# electrical_scheme.net
KiCad netlist of a schematic drawn in EAGLE
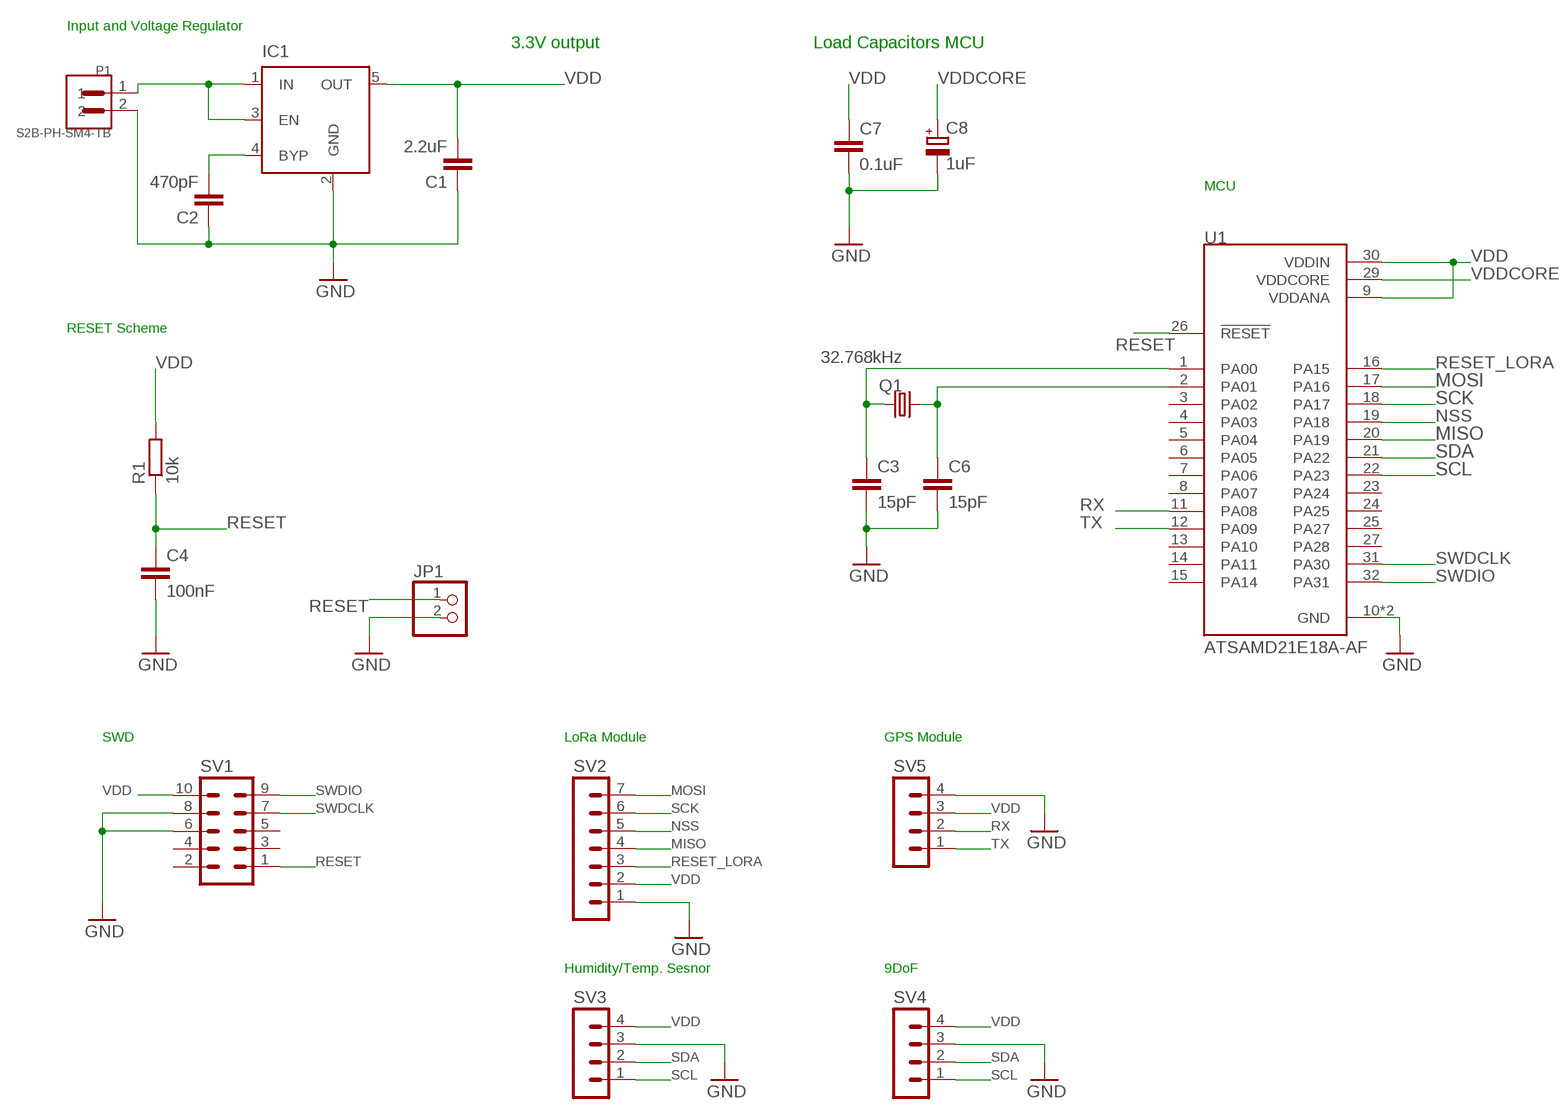
[diagram p0: schematic, sheet 1]

(export (version "E")
  (design (tool "Eeschema 10.0.6"))
  (components
    (comp (ref "C1")
      (value "2.2uF")
      (footprint "eagle-import:C1608")
      (libsource (lib "eagle-import") (part "C-EUC1608"))
    )
    (comp (ref "C2")
      (value "470pF")
      (footprint "eagle-import:C1608")
      (libsource (lib "eagle-import") (part "C-EUC1608"))
    )
    (comp (ref "C3")
      (value "15pF")
      (footprint "eagle-import:C1608")
      (libsource (lib "eagle-import") (part "C-EUC1608"))
    )
    (comp (ref "C4")
      (value "100nF")
      (footprint "eagle-import:C1608")
      (libsource (lib "eagle-import") (part "C-EUC1608"))
    )
    (comp (ref "C6")
      (value "15pF")
      (footprint "eagle-import:C1608")
      (libsource (lib "eagle-import") (part "C-EUC1608"))
    )
    (comp (ref "C7")
      (value "0.1uF")
      (footprint "eagle-import:C1608")
      (libsource (lib "eagle-import") (part "C-EUC1608"))
    )
    (comp (ref "C8")
      (value "1uF")
      (footprint "eagle-import:C_6032-28R")
      (libsource (lib "eagle-import") (part "CPOL-EUC/6032-28R"))
    )
    (comp (ref "IC1")
      (value "MIC5219XX")
      (footprint "eagle-import:SOT23-5")
      (libsource (lib "eagle-import") (part "MIC5219XX"))
    )
    (comp (ref "JP1")
      (value "PINHD-1X2")
      (footprint "eagle-import:1X02")
      (libsource (lib "eagle-import") (part "PINHD-1X2"))
    )
    (comp (ref "P1")
      (value "S2B-PH-SM4-TB")
      (footprint "eagle-import:JST_S2B-PH-SM4-TB")
      (fields (field (name "MF") "JST Sales"))
      (libsource (lib "eagle-import") (part "S2B-PH-SM4-TB"))
    )
    (comp (ref "Q1")
      (value "32.768kHz")
      (footprint "eagle-import:MC-306")
      (fields (field (name "MPN") "MC-306 60.0KHZ  100PPM ,12.5PF"))
      (libsource (lib "eagle-import") (part "MC-306"))
    )
    (comp (ref "R1")
      (value "10k")
      (footprint "eagle-import:R0805")
      (libsource (lib "eagle-import") (part "R-EU_R0805"))
    )
    (comp (ref "SV1")
      (value "MA05-2")
      (footprint "eagle-import:MA05-2")
      (libsource (lib "eagle-import") (part "MA05-2"))
    )
    (comp (ref "SV2")
      (value "MA07-1")
      (footprint "eagle-import:MA07-1")
      (libsource (lib "eagle-import") (part "MA07-1"))
    )
    (comp (ref "SV3")
      (value "MA04-1")
      (footprint "eagle-import:MA04-1")
      (libsource (lib "eagle-import") (part "MA04-1"))
    )
    (comp (ref "SV4")
      (value "MA04-1")
      (footprint "eagle-import:MA04-1")
      (libsource (lib "eagle-import") (part "MA04-1"))
    )
    (comp (ref "SV5")
      (value "MA04-1")
      (footprint "eagle-import:MA04-1")
      (libsource (lib "eagle-import") (part "MA04-1"))
    )
    (comp (ref "U1")
      (value "ATSAMD21E18A-AF")
      (footprint "eagle-import:QFP80P900X900X120-32N")
      (fields (field (name "MF") "Microchip"))
      (libsource (lib "eagle-import") (part "ATSAMD21E18A-AF"))
    )
  )
  (nets
    (net (code "1") (name "/MISO") (class "Default")
      (node (ref "SV2") (pin "4") (pinfunction "4_4") (pintype "passive"))
      (node (ref "U1") (pin "20") (pinfunction "PA19_20") (pintype "bidirectional"))
    )
    (net (code "2") (name "/MOSI") (class "Default")
      (node (ref "SV2") (pin "7") (pinfunction "7_7") (pintype "passive"))
      (node (ref "U1") (pin "17") (pinfunction "PA16_17") (pintype "bidirectional"))
    )
    (net (code "3") (name "/NSS") (class "Default")
      (node (ref "SV2") (pin "5") (pinfunction "5_5") (pintype "passive"))
      (node (ref "U1") (pin "19") (pinfunction "PA18_19") (pintype "bidirectional"))
    )
    (net (code "4") (name "/RESET") (class "Default")
      (node (ref "C4") (pin "1") (pinfunction "1_1") (pintype "passive"))
      (node (ref "JP1") (pin "1") (pinfunction "1_1") (pintype "passive"))
      (node (ref "R1") (pin "1") (pinfunction "1_1") (pintype "passive"))
      (node (ref "SV1") (pin "1") (pinfunction "1_1") (pintype "passive"))
      (node (ref "U1") (pin "26") (pinfunction "~{RESET}_26") (pintype "input"))
    )
    (net (code "5") (name "/RESET_LORA") (class "Default")
      (node (ref "SV2") (pin "3") (pinfunction "3_3") (pintype "passive"))
      (node (ref "U1") (pin "16") (pinfunction "PA15_16") (pintype "bidirectional"))
    )
    (net (code "6") (name "/RX") (class "Default")
      (node (ref "SV5") (pin "2") (pinfunction "2_2") (pintype "passive"))
      (node (ref "U1") (pin "11") (pinfunction "PA08_11") (pintype "bidirectional"))
    )
    (net (code "7") (name "/SCK") (class "Default")
      (node (ref "SV2") (pin "6") (pinfunction "6_6") (pintype "passive"))
      (node (ref "U1") (pin "18") (pinfunction "PA17_18") (pintype "bidirectional"))
    )
    (net (code "8") (name "/SCL") (class "Default")
      (node (ref "SV3") (pin "1") (pinfunction "1_1") (pintype "passive"))
      (node (ref "SV4") (pin "1") (pinfunction "1_1") (pintype "passive"))
      (node (ref "U1") (pin "22") (pinfunction "PA23_22") (pintype "bidirectional"))
    )
    (net (code "9") (name "/SDA") (class "Default")
      (node (ref "SV3") (pin "2") (pinfunction "2_2") (pintype "passive"))
      (node (ref "SV4") (pin "2") (pinfunction "2_2") (pintype "passive"))
      (node (ref "U1") (pin "21") (pinfunction "PA22_21") (pintype "bidirectional"))
    )
    (net (code "10") (name "/SWDCLK") (class "Default")
      (node (ref "SV1") (pin "7") (pinfunction "7_7") (pintype "passive"))
      (node (ref "U1") (pin "31") (pinfunction "PA30_31") (pintype "bidirectional"))
    )
    (net (code "11") (name "/SWDIO") (class "Default")
      (node (ref "SV1") (pin "9") (pinfunction "9_9") (pintype "passive"))
      (node (ref "U1") (pin "32") (pinfunction "PA31_32") (pintype "bidirectional"))
    )
    (net (code "12") (name "/TX") (class "Default")
      (node (ref "SV5") (pin "1") (pinfunction "1_1") (pintype "passive"))
      (node (ref "U1") (pin "12") (pinfunction "PA09_12") (pintype "bidirectional"))
    )
    (net (code "13") (name "/VDD") (class "Default")
      (node (ref "C1") (pin "2") (pinfunction "2_2") (pintype "passive"))
      (node (ref "C7") (pin "1") (pinfunction "1_1") (pintype "passive"))
      (node (ref "IC1") (pin "5") (pinfunction "OUT_5") (pintype "output"))
      (node (ref "R1") (pin "2") (pinfunction "2_2") (pintype "passive"))
      (node (ref "SV1") (pin "10") (pinfunction "10_10") (pintype "passive"))
      (node (ref "SV2") (pin "2") (pinfunction "2_2") (pintype "passive"))
      (node (ref "SV3") (pin "4") (pinfunction "4_4") (pintype "passive"))
      (node (ref "SV4") (pin "4") (pinfunction "4_4") (pintype "passive"))
      (node (ref "SV5") (pin "3") (pinfunction "3_3") (pintype "passive"))
      (node (ref "U1") (pin "30") (pinfunction "VDDIN_30") (pintype "power_in"))
      (node (ref "U1") (pin "9") (pinfunction "VDDANA_9") (pintype "power_in"))
    )
    (net (code "14") (name "/VDDCORE") (class "Default")
      (node (ref "C8") (pin "+") (pinfunction "+_+") (pintype "passive"))
      (node (ref "U1") (pin "29") (pinfunction "VDDCORE_29") (pintype "power_in"))
    )
    (net (code "15") (name "GND") (class "Default")
      (node (ref "C1") (pin "1") (pinfunction "1_1") (pintype "passive"))
      (node (ref "C2") (pin "1") (pinfunction "1_1") (pintype "passive"))
      (node (ref "C3") (pin "2") (pinfunction "2_2") (pintype "passive"))
      (node (ref "C4") (pin "2") (pinfunction "2_2") (pintype "passive"))
      (node (ref "C6") (pin "2") (pinfunction "2_2") (pintype "passive"))
      (node (ref "C7") (pin "2") (pinfunction "2_2") (pintype "passive"))
      (node (ref "C8") (pin "-") (pinfunction "-_-") (pintype "passive"))
      (node (ref "IC1") (pin "2") (pinfunction "GND_2") (pintype "power_in"))
      (node (ref "JP1") (pin "2") (pinfunction "2_2") (pintype "passive"))
      (node (ref "P1") (pin "2") (pinfunction "2_2") (pintype "passive"))
      (node (ref "SV1") (pin "6") (pinfunction "6_6") (pintype "passive"))
      (node (ref "SV1") (pin "8") (pinfunction "8_8") (pintype "passive"))
      (node (ref "SV2") (pin "1") (pinfunction "1_1") (pintype "passive"))
      (node (ref "SV3") (pin "3") (pinfunction "3_3") (pintype "passive"))
      (node (ref "SV4") (pin "3") (pinfunction "3_3") (pintype "passive"))
      (node (ref "SV5") (pin "4") (pinfunction "4_4") (pintype "passive"))
      (node (ref "U1") (pin "10") (pinfunction "GND_10") (pintype "power_in"))
      (node (ref "U1") (pin "28") (pinfunction "GND_28") (pintype "power_in"))
    )
    (net (code "16") (name "Net-(IC1-BYP)") (class "Default")
      (node (ref "C2") (pin "2") (pinfunction "2_2") (pintype "passive"))
      (node (ref "IC1") (pin "4") (pinfunction "BYP_4") (pintype "passive"))
    )
    (net (code "17") (name "Net-(IC1-EN)") (class "Default")
      (node (ref "IC1") (pin "1") (pinfunction "IN_1") (pintype "input"))
      (node (ref "IC1") (pin "3") (pinfunction "EN_3") (pintype "input"))
      (node (ref "P1") (pin "1") (pinfunction "1_1") (pintype "passive"))
    )
    (net (code "18") (name "Net-(Q1-2)") (class "Default")
      (node (ref "C6") (pin "1") (pinfunction "1_1") (pintype "passive"))
      (node (ref "Q1") (pin "4") (pinfunction "2_4") (pintype "passive"))
      (node (ref "U1") (pin "2") (pinfunction "PA01_2") (pintype "bidirectional"))
    )
    (net (code "19") (name "Net-(U1-PA00)") (class "Default")
      (node (ref "C3") (pin "1") (pinfunction "1_1") (pintype "passive"))
      (node (ref "Q1") (pin "1") (pinfunction "1_1") (pintype "passive"))
      (node (ref "U1") (pin "1") (pinfunction "PA00_1") (pintype "bidirectional"))
    )
    (net (code "20") (name "unconnected-(SV1-Pad2)") (class "Default")
      (node (ref "SV1") (pin "2") (pinfunction "2_2") (pintype "passive"))
    )
    (net (code "21") (name "unconnected-(SV1-Pad3)") (class "Default")
      (node (ref "SV1") (pin "3") (pinfunction "3_3") (pintype "passive"))
    )
    (net (code "22") (name "unconnected-(SV1-Pad4)") (class "Default")
      (node (ref "SV1") (pin "4") (pinfunction "4_4") (pintype "passive"))
    )
    (net (code "23") (name "unconnected-(SV1-Pad5)") (class "Default")
      (node (ref "SV1") (pin "5") (pinfunction "5_5") (pintype "passive"))
    )
    (net (code "24") (name "unconnected-(U1-PA02-Pad3)") (class "Default")
      (node (ref "U1") (pin "3") (pinfunction "PA02_3") (pintype "bidirectional"))
    )
    (net (code "25") (name "unconnected-(U1-PA03-Pad4)") (class "Default")
      (node (ref "U1") (pin "4") (pinfunction "PA03_4") (pintype "bidirectional"))
    )
    (net (code "26") (name "unconnected-(U1-PA04-Pad5)") (class "Default")
      (node (ref "U1") (pin "5") (pinfunction "PA04_5") (pintype "bidirectional"))
    )
    (net (code "27") (name "unconnected-(U1-PA05-Pad6)") (class "Default")
      (node (ref "U1") (pin "6") (pinfunction "PA05_6") (pintype "bidirectional"))
    )
    (net (code "28") (name "unconnected-(U1-PA06-Pad7)") (class "Default")
      (node (ref "U1") (pin "7") (pinfunction "PA06_7") (pintype "bidirectional"))
    )
    (net (code "29") (name "unconnected-(U1-PA07-Pad8)") (class "Default")
      (node (ref "U1") (pin "8") (pinfunction "PA07_8") (pintype "bidirectional"))
    )
    (net (code "30") (name "unconnected-(U1-PA10-Pad13)") (class "Default")
      (node (ref "U1") (pin "13") (pinfunction "PA10_13") (pintype "bidirectional"))
    )
    (net (code "31") (name "unconnected-(U1-PA11-Pad14)") (class "Default")
      (node (ref "U1") (pin "14") (pinfunction "PA11_14") (pintype "bidirectional"))
    )
    (net (code "32") (name "unconnected-(U1-PA14-Pad15)") (class "Default")
      (node (ref "U1") (pin "15") (pinfunction "PA14_15") (pintype "bidirectional"))
    )
    (net (code "33") (name "unconnected-(U1-PA24-Pad23)") (class "Default")
      (node (ref "U1") (pin "23") (pinfunction "PA24_23") (pintype "bidirectional"))
    )
    (net (code "34") (name "unconnected-(U1-PA25-Pad24)") (class "Default")
      (node (ref "U1") (pin "24") (pinfunction "PA25_24") (pintype "bidirectional"))
    )
    (net (code "35") (name "unconnected-(U1-PA27-Pad25)") (class "Default")
      (node (ref "U1") (pin "25") (pinfunction "PA27_25") (pintype "bidirectional"))
    )
    (net (code "36") (name "unconnected-(U1-PA28-Pad27)") (class "Default")
      (node (ref "U1") (pin "27") (pinfunction "PA28_27") (pintype "bidirectional"))
    )
  )
)
